# ToF_Sensor.net
KiCad netlist of a schematic drawn in Altium Designer
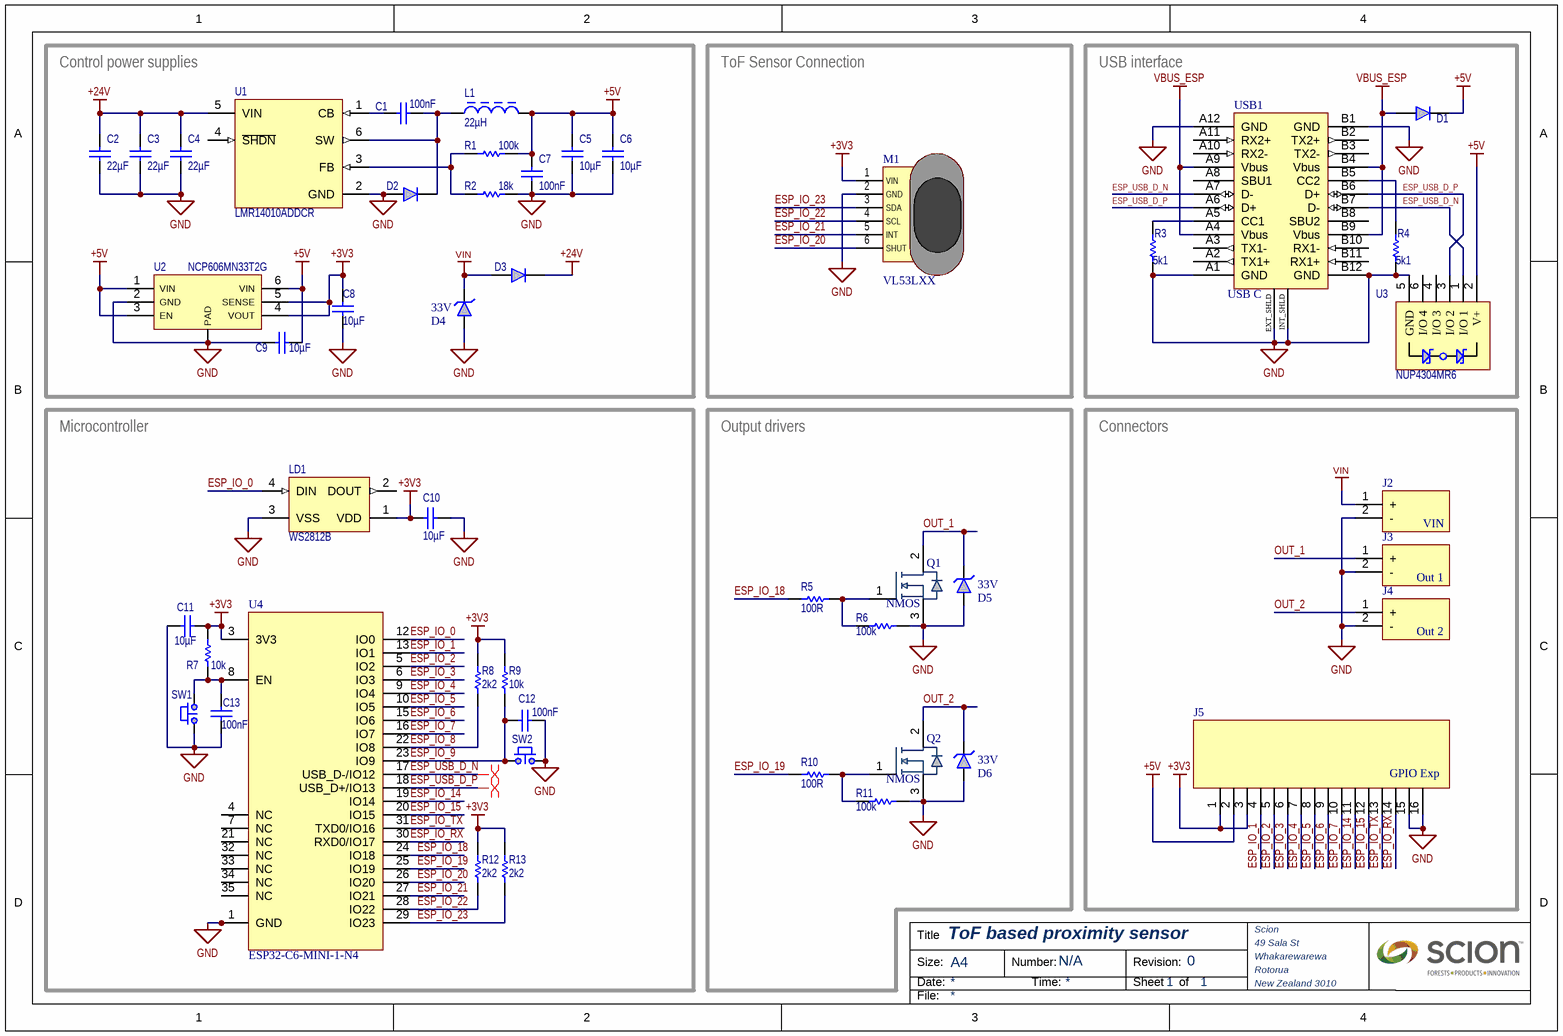
[diagram p0: ToF Sensor.SchDoc]

(export (version "E")
  (design (tool "Eeschema 10.0.6"))
  (components
    (comp (ref "C1")
      (value "100nF")
      (footprint "0603_CAP")
      (description "SMD Capacitor")
      (fields (field (name "Comment") "Capacitor"))
      (libsource (lib "Scion Research") (part "CMP-019-00005-2"))
    )
    (comp (ref "C2")
      (value "22µF")
      (footprint "1206_CAP")
      (description "SMD Capacitor")
      (fields (field (name "Comment") "Capacitor"))
      (libsource (lib "Scion Research") (part "CMP-019-00005-2"))
    )
    (comp (ref "C3")
      (value "22µF")
      (footprint "1206_CAP")
      (description "SMD Capacitor")
      (fields (field (name "Comment") "Capacitor"))
      (libsource (lib "Scion Research") (part "CMP-019-00005-2"))
    )
    (comp (ref "C4")
      (value "22µF")
      (footprint "1206_CAP")
      (description "SMD Capacitor")
      (fields (field (name "Comment") "Capacitor"))
      (libsource (lib "Scion Research") (part "CMP-019-00005-2"))
    )
    (comp (ref "C5")
      (value "10µF")
      (footprint "0603_CAP")
      (description "SMD Capacitor")
      (fields (field (name "Comment") "Capacitor"))
      (libsource (lib "Scion Research") (part "CMP-019-00005-2"))
    )
    (comp (ref "C6")
      (value "10µF")
      (footprint "0603_CAP")
      (description "SMD Capacitor")
      (fields (field (name "Comment") "Capacitor"))
      (libsource (lib "Scion Research") (part "CMP-019-00005-2"))
    )
    (comp (ref "C7")
      (value "100nF")
      (footprint "0603_CAP")
      (description "SMD Capacitor")
      (fields (field (name "Comment") "Capacitor"))
      (libsource (lib "Scion Research") (part "CMP-019-00005-2"))
    )
    (comp (ref "C8")
      (value "10µF")
      (footprint "0603_CAP")
      (description "SMD Capacitor")
      (fields (field (name "Comment") "Capacitor"))
      (libsource (lib "Scion Research") (part "CMP-019-00005-2"))
    )
    (comp (ref "C9")
      (value "10µF")
      (footprint "0603_CAP")
      (description "SMD Capacitor")
      (fields (field (name "Comment") "Capacitor"))
      (libsource (lib "Scion Research") (part "CMP-019-00005-2"))
    )
    (comp (ref "C10")
      (value "10µF")
      (footprint "0603_CAP")
      (description "SMD Capacitor")
      (fields (field (name "Comment") "Capacitor"))
      (libsource (lib "Scion Research") (part "CMP-019-00005-2"))
    )
    (comp (ref "C11")
      (value "10µF")
      (footprint "0603_CAP")
      (description "SMD Capacitor")
      (fields (field (name "Comment") "Capacitor"))
      (libsource (lib "Scion Research") (part "CMP-019-00005-2"))
    )
    (comp (ref "C12")
      (value "100nF")
      (footprint "0603_CAP")
      (description "SMD Capacitor")
      (fields (field (name "Comment") "Capacitor"))
      (libsource (lib "Scion Research") (part "CMP-019-00005-2"))
    )
    (comp (ref "C13")
      (value "100nF")
      (footprint "0603_CAP")
      (description "SMD Capacitor")
      (fields (field (name "Comment") "Capacitor"))
      (libsource (lib "Scion Research") (part "CMP-019-00005-2"))
    )
    (comp (ref "D1")
      (value "Diode")
      (footprint "SOD-123")
      (description "SMD Diode")
      (libsource (lib "Scion Research") (part "Diode"))
    )
    (comp (ref "D2")
      (value "Diode")
      (footprint "SOD-123")
      (description "SMD Diode")
      (libsource (lib "Scion Research") (part "Diode"))
    )
    (comp (ref "D3")
      (value "Diode")
      (footprint "SOD-123")
      (description "SMD Diode")
      (libsource (lib "Scion Research") (part "Diode"))
    )
    (comp (ref "D4")
      (value "Transil")
      (footprint "SMBJ")
      (description "Transient Voltage Suppressor")
      (fields (field (name "BREAKDOWN VOLTAGE") "33V"))
      (libsource (lib "Scion Research") (part "CMP-004-0042-1"))
    )
    (comp (ref "D5")
      (value "Transil")
      (footprint "SMBJ")
      (description "Transient Voltage Suppressor")
      (fields (field (name "BREAKDOWN VOLTAGE") "33V"))
      (libsource (lib "Scion Research") (part "CMP-004-0042-1"))
    )
    (comp (ref "D6")
      (value "Transil")
      (footprint "SMBJ")
      (description "Transient Voltage Suppressor")
      (fields (field (name "BREAKDOWN VOLTAGE") "33V"))
      (libsource (lib "Scion Research") (part "CMP-004-0042-1"))
    )
    (comp (ref "J2")
      (value "VIN")
      (footprint "2P 3.5mm Phoenix screw terminal 1988972")
      (description "2 Pin Connector")
      (libsource (lib "Scion Research") (part "CMP-002-00074-8"))
    )
    (comp (ref "J3")
      (value "Out 1")
      (footprint "2P 3.5mm Phoenix screw terminal 1988972")
      (description "2 Pin Connector")
      (libsource (lib "Scion Research") (part "CMP-002-00074-8"))
    )
    (comp (ref "J4")
      (value "Out 2")
      (footprint "2P 3.5mm Phoenix screw terminal 1988972")
      (description "2 Pin Connector")
      (libsource (lib "Scion Research") (part "CMP-002-00074-8"))
    )
    (comp (ref "J5")
      (value "GPIO Exp")
      (footprint "DIP16")
      (description "16 Pin Connector")
      (libsource (lib "Scion Research") (part "16_Pin_SIL"))
    )
    (comp (ref "L1")
      (value "22µH")
      (footprint "BOUR-SRN8040_V")
      (description "Power Inductor")
      (fields (field (name "Comment") "Inductor"))
      (libsource (lib "Scion Research") (part "Inductor"))
    )
    (comp (ref "LD1")
      (value "WS2812B")
      (footprint "WS2812B-2020")
      (fields (field (name "MANUFACTURER") "Adafruit Industries"))
      (libsource (lib "Scion Research") (part "CMP-007-00035-3"))
    )
    (comp (ref "M1")
      (value "VL53LXX")
      (footprint "VL53LXX-Footprint-1")
      (description "ST ToF sensor")
      (libsource (lib "Scion Research") (part "VL53LXX-Symbol-1"))
    )
    (comp (ref "Q1")
      (value "NMOS")
      (footprint "SOT-23")
      (description "N Channel MOSFET")
      (libsource (lib "Scion Research") (part "CMP-004-0025-1"))
    )
    (comp (ref "Q2")
      (value "NMOS")
      (footprint "SOT-23")
      (description "N Channel MOSFET")
      (libsource (lib "Scion Research") (part "CMP-004-0025-1"))
    )
    (comp (ref "R1")
      (value "Resistor")
      (footprint "0603_RES")
      (description "SMD Resistor")
      (fields (field (name "ALTIUM_VALUE") "100k"))
      (libsource (lib "Scion Research") (part "CMP-009-00177-2"))
    )
    (comp (ref "R2")
      (value "Resistor")
      (footprint "0603_RES")
      (description "SMD Resistor")
      (fields (field (name "ALTIUM_VALUE") "18k"))
      (libsource (lib "Scion Research") (part "CMP-009-00177-2"))
    )
    (comp (ref "R3")
      (value "Resistor")
      (footprint "0603_RES")
      (description "SMD Resistor")
      (fields (field (name "ALTIUM_VALUE") "5k1"))
      (libsource (lib "Scion Research") (part "CMP-009-00177-2"))
    )
    (comp (ref "R4")
      (value "Resistor")
      (footprint "0603_RES")
      (description "SMD Resistor")
      (fields (field (name "ALTIUM_VALUE") "5k1"))
      (libsource (lib "Scion Research") (part "CMP-009-00177-2"))
    )
    (comp (ref "R5")
      (value "100R")
      (footprint "0603_RES")
      (description "SMD Resistor")
      (fields (field (name "Comment") "Resistor"))
      (libsource (lib "Scion Research") (part "CMP-009-00177-2"))
    )
    (comp (ref "R6")
      (value "100k")
      (footprint "0603_RES")
      (description "SMD Resistor")
      (fields (field (name "Comment") "Resistor"))
      (libsource (lib "Scion Research") (part "CMP-009-00177-2"))
    )
    (comp (ref "R7")
      (value "10k")
      (footprint "0603_RES")
      (description "SMD Resistor")
      (fields (field (name "Comment") "Resistor"))
      (libsource (lib "Scion Research") (part "CMP-009-00177-2"))
    )
    (comp (ref "R8")
      (value "2k2")
      (footprint "0603_RES")
      (description "SMD Resistor")
      (fields (field (name "Comment") "Resistor"))
      (libsource (lib "Scion Research") (part "CMP-009-00177-2"))
    )
    (comp (ref "R9")
      (value "10k")
      (footprint "0603_RES")
      (description "SMD Resistor")
      (fields (field (name "Comment") "Resistor"))
      (libsource (lib "Scion Research") (part "CMP-009-00177-2"))
    )
    (comp (ref "R10")
      (value "100R")
      (footprint "0603_RES")
      (description "SMD Resistor")
      (fields (field (name "Comment") "Resistor"))
      (libsource (lib "Scion Research") (part "CMP-009-00177-2"))
    )
    (comp (ref "R11")
      (value "100k")
      (footprint "0603_RES")
      (description "SMD Resistor")
      (fields (field (name "Comment") "Resistor"))
      (libsource (lib "Scion Research") (part "CMP-009-00177-2"))
    )
    (comp (ref "R12")
      (value "2k2")
      (footprint "0603_RES")
      (description "SMD Resistor")
      (fields (field (name "Comment") "Resistor"))
      (libsource (lib "Scion Research") (part "CMP-009-00177-2"))
    )
    (comp (ref "R13")
      (value "2k2")
      (footprint "0603_RES")
      (description "SMD Resistor")
      (fields (field (name "Comment") "Resistor"))
      (libsource (lib "Scion Research") (part "CMP-009-00177-2"))
    )
    (comp (ref "SW1")
      (value "EVP-AAN02Q")
      (footprint "FP-EVP-AAN02Q-MFG")
      (description "Switch Tactile N.O. SPST Rectangular Button J-Bend 0.02A 15VDC 100000Cycles 5N SMD T/R")
      (libsource (lib "Scion Research") (part "67890d47754ac483cb1d3ba3be74b6c"))
    )
    (comp (ref "SW2")
      (value "EVP-AAN02Q")
      (footprint "FP-EVP-AAN02Q-MFG")
      (description "Switch Tactile N.O. SPST Rectangular Button J-Bend 0.02A 15VDC 100000Cycles 5N SMD T/R")
      (libsource (lib "Scion Research") (part "67890d47754ac483cb1d3ba3be74b6c"))
    )
    (comp (ref "U1")
      (value "LMR14010ADDCR")
      (footprint "FP-DDC0006A-IPC_A")
      (description "7-40VDC-DC buck converter")
      (libsource (lib "Scion Research") (part "LMR14010"))
    )
    (comp (ref "U2")
      (value "NCP606MN33T2G")
      (footprint "QFN95P330X295X100_HS-7N")
      (description "Fixed Positive LDO Regulator, 3.3V, 0.22V Dropout, CMOS")
      (libsource (lib "Scion Research") (part "NCP606MN33T2G-Symbol-1"))
    )
    (comp (ref "U3")
      (value "NUP4304MR6")
      (footprint "TSOP-6")
      (description "ESD Protection Doide Array")
      (libsource (lib "Scion Research") (part "CMP-004-0028-1"))
    )
    (comp (ref "U4")
      (value "ESP32-C6-MINI-1-N4")
      (footprint "ESP32-C6-MINI-1-N4-Footprint-1")
      (libsource (lib "Scion Research") (part "ESP32-C6-MINI-1-N4-Symbol-1"))
    )
    (comp (ref "USB1")
      (value "USB C")
      (footprint "GT-USB-7010ASV")
      (description "Vertical or RA Type C Usb Connector Rohs Compliant: Yes")
      (libsource (lib "Scion Research") (part "CMP-00005-5"))
    )
  )
  (nets
    (net (code "1") (name "+3V3") (class "Default")
      (node (ref "C10") (pin "1") (pinfunction "1_1") (pintype "passive"))
      (node (ref "C11") (pin "1") (pinfunction "1_1") (pintype "passive"))
      (node (ref "C8") (pin "1") (pinfunction "1_1") (pintype "passive"))
      (node (ref "J5") (pin "1") (pinfunction "1_1") (pintype "passive"))
      (node (ref "J5") (pin "3") (pinfunction "3_3") (pintype "passive"))
      (node (ref "LD1") (pin "1") (pinfunction "VDD_1") (pintype "power_in"))
      (node (ref "M1") (pin "1") (pinfunction "VIN_1") (pintype "passive"))
      (node (ref "R12") (pin "1") (pinfunction "1_1") (pintype "passive"))
      (node (ref "R13") (pin "1") (pinfunction "1_1") (pintype "passive"))
      (node (ref "R7") (pin "1") (pinfunction "1_1") (pintype "passive"))
      (node (ref "R8") (pin "1") (pinfunction "1_1") (pintype "passive"))
      (node (ref "R9") (pin "1") (pinfunction "1_1") (pintype "passive"))
      (node (ref "U2") (pin "4") (pinfunction "VOUT_4") (pintype "passive"))
      (node (ref "U2") (pin "5") (pinfunction "SENSE_5") (pintype "passive"))
      (node (ref "U4") (pin "3") (pinfunction "3V3_3") (pintype "passive"))
    )
    (net (code "2") (name "+5V") (class "Default")
      (node (ref "C5") (pin "1") (pinfunction "1_1") (pintype "passive"))
      (node (ref "C6") (pin "1") (pinfunction "1_1") (pintype "passive"))
      (node (ref "C7") (pin "1") (pinfunction "1_1") (pintype "passive"))
      (node (ref "C9") (pin "1") (pinfunction "1_1") (pintype "passive"))
      (node (ref "D1") (pin "1") (pinfunction "K_1") (pintype "passive"))
      (node (ref "J5") (pin "2") (pinfunction "2_2") (pintype "passive"))
      (node (ref "L1") (pin "2") (pinfunction "2_2") (pintype "passive"))
      (node (ref "R1") (pin "2") (pinfunction "2_2") (pintype "passive"))
      (node (ref "U2") (pin "1") (pinfunction "VIN_1") (pintype "passive"))
      (node (ref "U2") (pin "3") (pinfunction "EN_3") (pintype "passive"))
      (node (ref "U2") (pin "6") (pinfunction "VIN_6") (pintype "passive"))
      (node (ref "U3") (pin "2") (pinfunction "V+_2") (pintype "power_in"))
    )
    (net (code "3") (name "+24V") (class "Default")
      (node (ref "C2") (pin "1") (pinfunction "1_1") (pintype "passive"))
      (node (ref "C3") (pin "1") (pinfunction "1_1") (pintype "passive"))
      (node (ref "C4") (pin "1") (pinfunction "1_1") (pintype "passive"))
      (node (ref "D3") (pin "1") (pinfunction "K_1") (pintype "passive"))
      (node (ref "U1") (pin "5") (pinfunction "VIN_5") (pintype "power_in"))
    )
    (net (code "4") (name "/ESP_IO_0") (class "Default")
      (node (ref "LD1") (pin "4") (pinfunction "DIN_4") (pintype "input"))
      (node (ref "U4") (pin "12") (pinfunction "IO0_12") (pintype "passive"))
    )
    (net (code "5") (name "/ESP_IO_1") (class "Default")
      (node (ref "J5") (pin "4") (pinfunction "4_4") (pintype "passive"))
      (node (ref "U4") (pin "13") (pinfunction "IO1_13") (pintype "passive"))
    )
    (net (code "6") (name "/ESP_IO_2") (class "Default")
      (node (ref "J5") (pin "5") (pinfunction "5_5") (pintype "passive"))
      (node (ref "U4") (pin "5") (pinfunction "IO2_5") (pintype "passive"))
    )
    (net (code "7") (name "/ESP_IO_3") (class "Default")
      (node (ref "J5") (pin "6") (pinfunction "6_6") (pintype "passive"))
      (node (ref "U4") (pin "6") (pinfunction "IO3_6") (pintype "passive"))
    )
    (net (code "8") (name "/ESP_IO_4") (class "Default")
      (node (ref "J5") (pin "7") (pinfunction "7_7") (pintype "passive"))
      (node (ref "U4") (pin "9") (pinfunction "IO4_9") (pintype "passive"))
    )
    (net (code "9") (name "/ESP_IO_5") (class "Default")
      (node (ref "J5") (pin "8") (pinfunction "8_8") (pintype "passive"))
      (node (ref "U4") (pin "10") (pinfunction "IO5_10") (pintype "passive"))
    )
    (net (code "10") (name "/ESP_IO_6") (class "Default")
      (node (ref "J5") (pin "9") (pinfunction "9_9") (pintype "passive"))
      (node (ref "U4") (pin "15") (pinfunction "IO6_15") (pintype "passive"))
    )
    (net (code "11") (name "/ESP_IO_7") (class "Default")
      (node (ref "J5") (pin "10") (pinfunction "10_10") (pintype "passive"))
      (node (ref "U4") (pin "16") (pinfunction "IO7_16") (pintype "passive"))
    )
    (net (code "12") (name "/ESP_IO_8") (class "Default")
      (node (ref "R8") (pin "2") (pinfunction "2_2") (pintype "passive"))
      (node (ref "U4") (pin "22") (pinfunction "IO8_22") (pintype "passive"))
    )
    (net (code "13") (name "/ESP_IO_9") (class "Default")
      (node (ref "C12") (pin "1") (pinfunction "1_1") (pintype "passive"))
      (node (ref "R9") (pin "2") (pinfunction "2_2") (pintype "passive"))
      (node (ref "SW2") (pin "1") (pinfunction "1_1") (pintype "passive"))
      (node (ref "U4") (pin "23") (pinfunction "IO9_23") (pintype "passive"))
    )
    (net (code "14") (name "/ESP_IO_14") (class "Default")
      (node (ref "J5") (pin "11") (pinfunction "11_11") (pintype "passive"))
      (node (ref "U4") (pin "19") (pinfunction "IO14_19") (pintype "passive"))
    )
    (net (code "15") (name "/ESP_IO_15") (class "Default")
      (node (ref "J5") (pin "12") (pinfunction "12_12") (pintype "passive"))
      (node (ref "U4") (pin "20") (pinfunction "IO15_20") (pintype "passive"))
    )
    (net (code "16") (name "/ESP_IO_18") (class "Default")
      (node (ref "R5") (pin "1") (pinfunction "1_1") (pintype "passive"))
      (node (ref "U4") (pin "24") (pinfunction "IO18_24") (pintype "passive"))
    )
    (net (code "17") (name "/ESP_IO_19") (class "Default")
      (node (ref "R10") (pin "1") (pinfunction "1_1") (pintype "passive"))
      (node (ref "U4") (pin "25") (pinfunction "IO19_25") (pintype "passive"))
    )
    (net (code "18") (name "/ESP_IO_20") (class "Default")
      (node (ref "M1") (pin "6") (pinfunction "SHUT_6") (pintype "passive"))
      (node (ref "U4") (pin "26") (pinfunction "IO20_26") (pintype "passive"))
    )
    (net (code "19") (name "/ESP_IO_21") (class "Default")
      (node (ref "M1") (pin "5") (pinfunction "INT_5") (pintype "passive"))
      (node (ref "U4") (pin "27") (pinfunction "IO21_27") (pintype "passive"))
    )
    (net (code "20") (name "/ESP_IO_22") (class "Default")
      (node (ref "M1") (pin "4") (pinfunction "SCL_4") (pintype "passive"))
      (node (ref "R12") (pin "2") (pinfunction "2_2") (pintype "passive"))
      (node (ref "U4") (pin "28") (pinfunction "IO22_28") (pintype "passive"))
    )
    (net (code "21") (name "/ESP_IO_23") (class "Default")
      (node (ref "M1") (pin "3") (pinfunction "SDA_3") (pintype "passive"))
      (node (ref "R13") (pin "2") (pinfunction "2_2") (pintype "passive"))
      (node (ref "U4") (pin "29") (pinfunction "IO23_29") (pintype "passive"))
    )
    (net (code "22") (name "/ESP_IO_RX") (class "Default")
      (node (ref "J5") (pin "14") (pinfunction "14_14") (pintype "passive"))
      (node (ref "U4") (pin "30") (pinfunction "RXD0/IO17_30") (pintype "passive"))
    )
    (net (code "23") (name "/ESP_IO_TX") (class "Default")
      (node (ref "J5") (pin "13") (pinfunction "13_13") (pintype "passive"))
      (node (ref "U4") (pin "31") (pinfunction "TXD0/IO16_31") (pintype "passive"))
    )
    (net (code "24") (name "/ESP_USB_D_N") (class "Default")
      (node (ref "U3") (pin "1") (pinfunction "I/O_1_1") (pintype "power_in"))
      (node (ref "U4") (pin "17") (pinfunction "USB_D-/IO12_17") (pintype "passive"))
      (node (ref "USB1") (pin "A7") (pinfunction "D-_A7") (pintype "bidirectional"))
      (node (ref "USB1") (pin "B7") (pinfunction "D-_B7") (pintype "bidirectional"))
    )
    (net (code "25") (name "/ESP_USB_D_P") (class "Default")
      (node (ref "U3") (pin "3") (pinfunction "I/O_2_3") (pintype "power_in"))
      (node (ref "U4") (pin "18") (pinfunction "USB_D+/IO13_18") (pintype "passive"))
      (node (ref "USB1") (pin "A6") (pinfunction "D+_A6") (pintype "bidirectional"))
      (node (ref "USB1") (pin "B6") (pinfunction "D+_B6") (pintype "bidirectional"))
    )
    (net (code "26") (name "/OUT_1") (class "Default")
      (node (ref "D5") (pin "2") (pinfunction "K_2") (pintype "passive"))
      (node (ref "J3") (pin "1") (pinfunction "+_1") (pintype "passive"))
      (node (ref "Q1") (pin "2") (pinfunction "D_2") (pintype "passive"))
    )
    (net (code "27") (name "/OUT_2") (class "Default")
      (node (ref "D6") (pin "2") (pinfunction "K_2") (pintype "passive"))
      (node (ref "J4") (pin "1") (pinfunction "+_1") (pintype "passive"))
      (node (ref "Q2") (pin "2") (pinfunction "D_2") (pintype "passive"))
    )
    (net (code "28") (name "GND") (class "Default")
      (node (ref "C10") (pin "2") (pinfunction "2_2") (pintype "passive"))
      (node (ref "C11") (pin "2") (pinfunction "2_2") (pintype "passive"))
      (node (ref "C12") (pin "2") (pinfunction "2_2") (pintype "passive"))
      (node (ref "C13") (pin "2") (pinfunction "2_2") (pintype "passive"))
      (node (ref "C2") (pin "2") (pinfunction "2_2") (pintype "passive"))
      (node (ref "C3") (pin "2") (pinfunction "2_2") (pintype "passive"))
      (node (ref "C4") (pin "2") (pinfunction "2_2") (pintype "passive"))
      (node (ref "C5") (pin "2") (pinfunction "2_2") (pintype "passive"))
      (node (ref "C6") (pin "2") (pinfunction "2_2") (pintype "passive"))
      (node (ref "C7") (pin "2") (pinfunction "2_2") (pintype "passive"))
      (node (ref "C8") (pin "2") (pinfunction "2_2") (pintype "passive"))
      (node (ref "C9") (pin "2") (pinfunction "2_2") (pintype "passive"))
      (node (ref "D2") (pin "2") (pinfunction "A_2") (pintype "passive"))
      (node (ref "D4") (pin "1") (pinfunction "A_1") (pintype "passive"))
      (node (ref "D5") (pin "1") (pinfunction "A_1") (pintype "passive"))
      (node (ref "D6") (pin "1") (pinfunction "A_1") (pintype "passive"))
      (node (ref "J2") (pin "2") (pinfunction "-_2") (pintype "passive"))
      (node (ref "J3") (pin "2") (pinfunction "-_2") (pintype "passive"))
      (node (ref "J4") (pin "2") (pinfunction "-_2") (pintype "passive"))
      (node (ref "J5") (pin "15") (pinfunction "15_15") (pintype "passive"))
      (node (ref "J5") (pin "16") (pinfunction "16_16") (pintype "passive"))
      (node (ref "LD1") (pin "3") (pinfunction "VSS_3") (pintype "power_in"))
      (node (ref "M1") (pin "2") (pinfunction "GND_2") (pintype "passive"))
      (node (ref "Q1") (pin "3") (pinfunction "S_3") (pintype "passive"))
      (node (ref "Q2") (pin "3") (pinfunction "S_3") (pintype "passive"))
      (node (ref "R11") (pin "2") (pinfunction "2_2") (pintype "passive"))
      (node (ref "R2") (pin "2") (pinfunction "2_2") (pintype "passive"))
      (node (ref "R3") (pin "2") (pinfunction "2_2") (pintype "passive"))
      (node (ref "R4") (pin "2") (pinfunction "2_2") (pintype "passive"))
      (node (ref "R6") (pin "2") (pinfunction "2_2") (pintype "passive"))
      (node (ref "SW1") (pin "1") (pinfunction "1_1") (pintype "passive"))
      (node (ref "SW2") (pin "2") (pinfunction "2_2") (pintype "passive"))
      (node (ref "U1") (pin "2") (pinfunction "GND_2") (pintype "power_in"))
      (node (ref "U2") (pin "2") (pinfunction "GND_2") (pintype "passive"))
      (node (ref "U2") (pin "PAD") (pinfunction "PAD_PAD") (pintype "passive"))
      (node (ref "U3") (pin "5") (pinfunction "GND_5") (pintype "power_in"))
      (node (ref "U4") (pin "1") (pinfunction "GND_1") (pintype "passive"))
      (node (ref "U4") (pin "11") (pinfunction "GND_11") (pintype "passive"))
      (node (ref "U4") (pin "14") (pinfunction "GND_14") (pintype "passive"))
      (node (ref "U4") (pin "2") (pinfunction "GND_2") (pintype "passive"))
      (node (ref "U4") (pin "36") (pinfunction "GND_36") (pintype "passive"))
      (node (ref "U4") (pin "37") (pinfunction "GND_37") (pintype "passive"))
      (node (ref "U4") (pin "38") (pinfunction "GND_38") (pintype "passive"))
      (node (ref "U4") (pin "39") (pinfunction "GND_39") (pintype "passive"))
      (node (ref "U4") (pin "40") (pinfunction "GND_40") (pintype "passive"))
      (node (ref "U4") (pin "41") (pinfunction "GND_41") (pintype "passive"))
      (node (ref "U4") (pin "42") (pinfunction "GND_42") (pintype "passive"))
      (node (ref "U4") (pin "43") (pinfunction "GND_43") (pintype "passive"))
      (node (ref "U4") (pin "44") (pinfunction "GND_44") (pintype "passive"))
      (node (ref "U4") (pin "45") (pinfunction "GND_45") (pintype "passive"))
      (node (ref "U4") (pin "46") (pinfunction "GND_46") (pintype "passive"))
      (node (ref "U4") (pin "47") (pinfunction "GND_47") (pintype "passive"))
      (node (ref "U4") (pin "48") (pinfunction "GND_48") (pintype "passive"))
      (node (ref "U4") (pin "49") (pinfunction "GND_49") (pintype "passive"))
      (node (ref "U4") (pin "50") (pinfunction "GND_50") (pintype "passive"))
      (node (ref "U4") (pin "51") (pinfunction "GND_51") (pintype "passive"))
      (node (ref "U4") (pin "52") (pinfunction "GND_52") (pintype "passive"))
      (node (ref "U4") (pin "53") (pinfunction "GND_53") (pintype "passive"))
      (node (ref "USB1") (pin "A1") (pinfunction "GND_A1") (pintype "power_in"))
      (node (ref "USB1") (pin "A12") (pinfunction "GND_A12") (pintype "power_in"))
      (node (ref "USB1") (pin "B1") (pinfunction "GND_B1") (pintype "power_in"))
      (node (ref "USB1") (pin "B12") (pinfunction "GND_B12") (pintype "power_in"))
      (node (ref "USB1") (pin "EXT_SHLD") (pintype "passive"))
      (node (ref "USB1") (pin "INT_SHLD") (pintype "passive"))
    )
    (net (code "29") (name "Net-(D2-K)") (class "Default")
      (node (ref "C1") (pin "1") (pinfunction "1_1") (pintype "passive"))
      (node (ref "D2") (pin "1") (pinfunction "K_1") (pintype "passive"))
      (node (ref "L1") (pin "1") (pinfunction "1_1") (pintype "passive"))
      (node (ref "U1") (pin "6") (pinfunction "SW_6") (pintype "output"))
    )
    (net (code "30") (name "Net-(Q1-G)") (class "Default")
      (node (ref "Q1") (pin "1") (pinfunction "G_1") (pintype "passive"))
      (node (ref "R5") (pin "2") (pinfunction "2_2") (pintype "passive"))
      (node (ref "R6") (pin "1") (pinfunction "1_1") (pintype "passive"))
    )
    (net (code "31") (name "Net-(Q2-G)") (class "Default")
      (node (ref "Q2") (pin "1") (pinfunction "G_1") (pintype "passive"))
      (node (ref "R10") (pin "2") (pinfunction "2_2") (pintype "passive"))
      (node (ref "R11") (pin "1") (pinfunction "1_1") (pintype "passive"))
    )
    (net (code "32") (name "Net-(U1-CB)") (class "Default")
      (node (ref "C1") (pin "2") (pinfunction "2_2") (pintype "passive"))
      (node (ref "U1") (pin "1") (pinfunction "CB_1") (pintype "input"))
    )
    (net (code "33") (name "Net-(U1-FB)") (class "Default")
      (node (ref "R1") (pin "1") (pinfunction "1_1") (pintype "passive"))
      (node (ref "R2") (pin "1") (pinfunction "1_1") (pintype "passive"))
      (node (ref "U1") (pin "3") (pinfunction "FB_3") (pintype "input"))
    )
    (net (code "34") (name "Net-(U4-EN)") (class "Default")
      (node (ref "C13") (pin "1") (pinfunction "1_1") (pintype "passive"))
      (node (ref "R7") (pin "2") (pinfunction "2_2") (pintype "passive"))
      (node (ref "SW1") (pin "2") (pinfunction "2_2") (pintype "passive"))
      (node (ref "U4") (pin "8") (pinfunction "EN_8") (pintype "passive"))
    )
    (net (code "35") (name "Net-(USB1-CC1)") (class "Default")
      (node (ref "R3") (pin "1") (pinfunction "1_1") (pintype "passive"))
      (node (ref "USB1") (pin "A5") (pinfunction "CC1_A5") (pintype "passive"))
    )
    (net (code "36") (name "Net-(USB1-CC2)") (class "Default")
      (node (ref "R4") (pin "1") (pinfunction "1_1") (pintype "passive"))
      (node (ref "USB1") (pin "B5") (pinfunction "CC2_B5") (pintype "passive"))
    )
    (net (code "37") (name "VBUS_ESP") (class "Default")
      (node (ref "D1") (pin "2") (pinfunction "A_2") (pintype "passive"))
      (node (ref "USB1") (pin "A4") (pinfunction "Vbus_A4") (pintype "power_in"))
      (node (ref "USB1") (pin "A9") (pinfunction "Vbus_A9") (pintype "power_in"))
      (node (ref "USB1") (pin "B4") (pinfunction "Vbus_B4") (pintype "power_in"))
      (node (ref "USB1") (pin "B9") (pinfunction "Vbus_B9") (pintype "power_in"))
    )
    (net (code "38") (name "VIN") (class "Default")
      (node (ref "D3") (pin "2") (pinfunction "A_2") (pintype "passive"))
      (node (ref "D4") (pin "2") (pinfunction "K_2") (pintype "passive"))
      (node (ref "J2") (pin "1") (pinfunction "+_1") (pintype "passive"))
    )
    (net (code "39") (name "unconnected-(LD1-DOUT-Pad2)") (class "Default")
      (node (ref "LD1") (pin "2") (pinfunction "DOUT_2") (pintype "output"))
    )
    (net (code "40") (name "unconnected-(U1-~{SHDN}-Pad4)") (class "Default")
      (node (ref "U1") (pin "4") (pinfunction "~{SHDN}_4") (pintype "input"))
    )
    (net (code "41") (name "unconnected-(U3-I{slash}O_3-Pad4)") (class "Default")
      (node (ref "U3") (pin "4") (pinfunction "I/O_3_4") (pintype "power_in"))
    )
    (net (code "42") (name "unconnected-(U3-I{slash}O_4-Pad6)") (class "Default")
      (node (ref "U3") (pin "6") (pinfunction "I/O_4_6") (pintype "power_in"))
    )
    (net (code "43") (name "unconnected-(U4-NC-Pad4)") (class "Default")
      (node (ref "U4") (pin "4") (pinfunction "NC_4") (pintype "passive"))
    )
    (net (code "44") (name "unconnected-(U4-NC-Pad7)") (class "Default")
      (node (ref "U4") (pin "7") (pinfunction "NC_7") (pintype "passive"))
    )
    (net (code "45") (name "unconnected-(U4-NC-Pad21)") (class "Default")
      (node (ref "U4") (pin "21") (pinfunction "NC_21") (pintype "passive"))
    )
    (net (code "46") (name "unconnected-(U4-NC-Pad32)") (class "Default")
      (node (ref "U4") (pin "32") (pinfunction "NC_32") (pintype "passive"))
    )
    (net (code "47") (name "unconnected-(U4-NC-Pad33)") (class "Default")
      (node (ref "U4") (pin "33") (pinfunction "NC_33") (pintype "passive"))
    )
    (net (code "48") (name "unconnected-(U4-NC-Pad34)") (class "Default")
      (node (ref "U4") (pin "34") (pinfunction "NC_34") (pintype "passive"))
    )
    (net (code "49") (name "unconnected-(U4-NC-Pad35)") (class "Default")
      (node (ref "U4") (pin "35") (pinfunction "NC_35") (pintype "passive"))
    )
    (net (code "50") (name "unconnected-(USB1-RX1+-PadB11)") (class "Default")
      (node (ref "USB1") (pin "B11") (pinfunction "RX1+_B11") (pintype "input"))
    )
    (net (code "51") (name "unconnected-(USB1-RX1--PadB10)") (class "Default")
      (node (ref "USB1") (pin "B10") (pinfunction "RX1-_B10") (pintype "input"))
    )
    (net (code "52") (name "unconnected-(USB1-RX2+-PadA11)") (class "Default")
      (node (ref "USB1") (pin "A11") (pinfunction "RX2+_A11") (pintype "input"))
    )
    (net (code "53") (name "unconnected-(USB1-RX2--PadA10)") (class "Default")
      (node (ref "USB1") (pin "A10") (pinfunction "RX2-_A10") (pintype "input"))
    )
    (net (code "54") (name "unconnected-(USB1-SBU1-PadA8)") (class "Default")
      (node (ref "USB1") (pin "A8") (pinfunction "SBU1_A8") (pintype "passive"))
    )
    (net (code "55") (name "unconnected-(USB1-SBU2-PadB8)") (class "Default")
      (node (ref "USB1") (pin "B8") (pinfunction "SBU2_B8") (pintype "passive"))
    )
    (net (code "56") (name "unconnected-(USB1-TX1+-PadA2)") (class "Default")
      (node (ref "USB1") (pin "A2") (pinfunction "TX1+_A2") (pintype "output"))
    )
    (net (code "57") (name "unconnected-(USB1-TX1--PadA3)") (class "Default")
      (node (ref "USB1") (pin "A3") (pinfunction "TX1-_A3") (pintype "output"))
    )
    (net (code "58") (name "unconnected-(USB1-TX2+-PadB2)") (class "Default")
      (node (ref "USB1") (pin "B2") (pinfunction "TX2+_B2") (pintype "output"))
    )
    (net (code "59") (name "unconnected-(USB1-TX2--PadB3)") (class "Default")
      (node (ref "USB1") (pin "B3") (pinfunction "TX2-_B3") (pintype "output"))
    )
  )
)
